# power_switch.net
KiCad netlist of a schematic drawn in Altium Designer
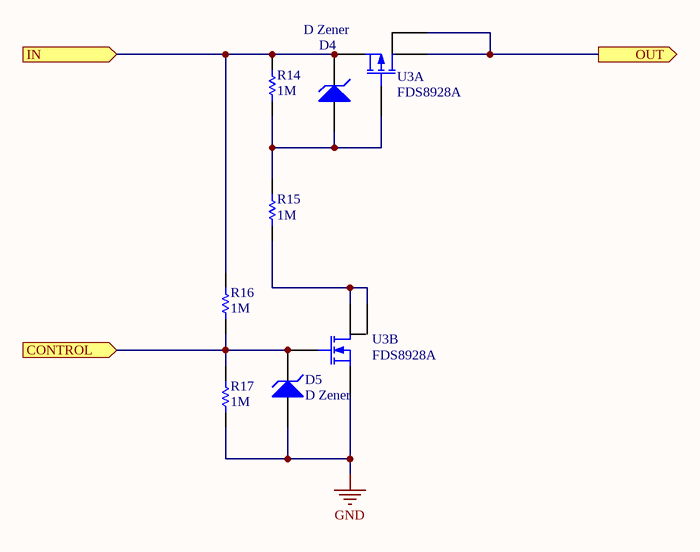
[diagram p0: power_switch.SchDoc]

(export (version "E")
  (design (tool "Eeschema 10.0.6"))
  (components
    (comp (ref "D4")
      (value "D Zener")
      (footprint "MM3Z")
      (description "Zener Diode")
      (fields (field (name "PUBLISHER") "Altium Limited"))
      (libsource (lib "Miscellaneous Devices") (part "D Zener"))
    )
    (comp (ref "D5")
      (value "D Zener")
      (footprint "MM3Z")
      (description "Zener Diode")
      (fields (field (name "PUBLISHER") "Altium Limited"))
      (libsource (lib "Miscellaneous Devices") (part "D Zener"))
    )
    (comp (ref "R14")
      (value "1M")
      (footprint "R0603")
      (description "Resistor")
      (fields (field (name "PUBLISHER") "Altium Limited"))
      (libsource (lib "Miscellaneous Devices") (part "Res1"))
    )
    (comp (ref "R15")
      (value "1M")
      (footprint "R0603")
      (description "Resistor")
      (fields (field (name "PUBLISHER") "Altium Limited"))
      (libsource (lib "Miscellaneous Devices") (part "Res1"))
    )
    (comp (ref "R16")
      (value "1M")
      (footprint "R0603")
      (description "Resistor")
      (fields (field (name "PUBLISHER") "Altium Limited"))
      (libsource (lib "Miscellaneous Devices") (part "Res1"))
    )
    (comp (ref "R17")
      (value "1M")
      (footprint "R0603")
      (description "Resistor")
      (fields (field (name "PUBLISHER") "Altium Limited"))
      (libsource (lib "Miscellaneous Devices") (part "Res1"))
    )
    (comp (ref "U3")
      (value "FDS8928A")
      (footprint "FDS8928A")
      (description "MOSFET, DUAL, NP, SMD, 8-SOIC")
      (libsource (lib "FDS8928A (N-P dual MOSFET)") (part "FDS8928A"))
    )
  )
  (nets
    (net (code "1") (name "/CONTROL") (class "Default")
      (node (ref "D5") (pin "2") (pinfunction "K_2") (pintype "passive"))
      (node (ref "R16") (pin "1") (pinfunction "1_1") (pintype "passive"))
      (node (ref "R17") (pin "2") (pinfunction "2_2") (pintype "passive"))
      (node (ref "U3") (pin "2") (pinfunction "G_N_2") (pintype "passive"))
    )
    (net (code "2") (name "/IN") (class "Default")
      (node (ref "D4") (pin "2") (pinfunction "K_2") (pintype "passive"))
      (node (ref "R14") (pin "2") (pinfunction "2_2") (pintype "passive"))
      (node (ref "R16") (pin "2") (pinfunction "2_2") (pintype "passive"))
      (node (ref "U3") (pin "3") (pinfunction "S_P_3") (pintype "passive"))
    )
    (net (code "3") (name "/OUT") (class "Default")
      (node (ref "U3") (pin "5") (pinfunction "D_P_5") (pintype "passive"))
      (node (ref "U3") (pin "6") (pinfunction "D_N_6") (pintype "passive"))
    )
    (net (code "4") (name "GND") (class "Default")
      (node (ref "D5") (pin "1") (pinfunction "A_1") (pintype "passive"))
      (node (ref "R17") (pin "1") (pinfunction "1_1") (pintype "passive"))
      (node (ref "U3") (pin "1") (pinfunction "S_N_1") (pintype "passive"))
    )
    (net (code "5") (name "Net-(D4-A)") (class "Default")
      (node (ref "D4") (pin "1") (pinfunction "A_1") (pintype "passive"))
      (node (ref "R14") (pin "1") (pinfunction "1_1") (pintype "passive"))
      (node (ref "R15") (pin "2") (pinfunction "2_2") (pintype "passive"))
      (node (ref "U3") (pin "4") (pinfunction "G_P_4") (pintype "passive"))
    )
    (net (code "6") (name "Net-(R15-Pad1)") (class "Default")
      (node (ref "R15") (pin "1") (pinfunction "1_1") (pintype "passive"))
      (node (ref "U3") (pin "7") (pinfunction "D_N_7") (pintype "passive"))
      (node (ref "U3") (pin "8") (pinfunction "D_N_8") (pintype "passive"))
    )
  )
)
